# SOS.net
KiCad netlist of a schematic drawn in EAGLE
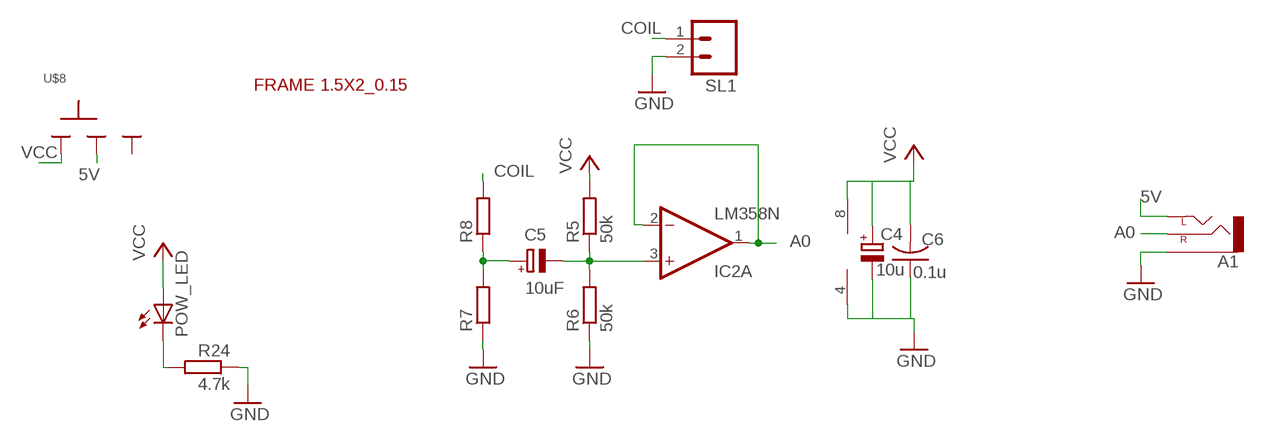
[diagram p0: schematic, sheet 1]

(export (version "E")
  (design (tool "Eeschema 10.0.6"))
  (components
    (comp (ref "A1")
      (value "AUDIO-JACKPTH")
      (footprint "eagle-import:AUDIO-JACK")
      (libsource (lib "eagle-import") (part "AUDIO-JACKPTH"))
    )
    (comp (ref "C4")
      (value "10u")
      (footprint "eagle-import:E2,5-5")
      (libsource (lib "eagle-import") (part "CPOL-EUE2.5-5"))
    )
    (comp (ref "C5")
      (value "10uF")
      (footprint "eagle-import:E2,5-6")
      (libsource (lib "eagle-import") (part "CPOL-EUE2.5-6"))
    )
    (comp (ref "C6")
      (value "0.1u")
      (footprint "eagle-import:C025-024X044")
      (libsource (lib "eagle-import") (part "C-US025-024X044"))
    )
    (comp (ref "IC2")
      (value "LM358N")
      (footprint "eagle-import:DIL08")
      (libsource (lib "eagle-import") (part "LM358N"))
    )
    (comp (ref "POW_LED")
      (value "LED3MM")
      (footprint "eagle-import:LED3MM")
      (libsource (lib "eagle-import") (part "LED3MM"))
    )
    (comp (ref "R5")
      (value "50k")
      (footprint "eagle-import:0204_7")
      (libsource (lib "eagle-import") (part "R-EU_0204/7"))
    )
    (comp (ref "R6")
      (value "50k")
      (footprint "eagle-import:0204_7")
      (libsource (lib "eagle-import") (part "R-EU_0204/7"))
    )
    (comp (ref "R7")
      (value "R-EU_0204/7")
      (footprint "eagle-import:0204_7")
      (libsource (lib "eagle-import") (part "R-EU_0204/7"))
    )
    (comp (ref "R8")
      (value "R-EU_0204/7")
      (footprint "eagle-import:0204_7")
      (libsource (lib "eagle-import") (part "R-EU_0204/7"))
    )
    (comp (ref "R24")
      (value "4.7k")
      (footprint "eagle-import:0204_7")
      (libsource (lib "eagle-import") (part "R-EU_0204/7"))
    )
    (comp (ref "SL1")
      (value "M02")
      (footprint "eagle-import:02P")
      (libsource (lib "eagle-import") (part "M02"))
    )
    (comp (ref "U$1")
      (value "FRAME_1.5X2_RAD_0.15")
      (footprint "eagle-import:FRAME_1.5X2_RAD_0.15")
      (libsource (lib "eagle-import") (part "FRAME_1.5X2_RAD_0.15"))
    )
    (comp (ref "U$8")
      (value "SLIDESWITCH-BIG")
      (footprint "eagle-import:BIGSWITCH")
      (libsource (lib "eagle-import") (part "SLIDESWITCH-BIG"))
    )
  )
  (nets
    (net (code "1") (name "/5V") (class "Default")
      (node (ref "A1") (pin "TIP") (pinfunction "LEFT_TIP") (pintype "bidirectional"))
      (node (ref "U$8") (pin "2") (pinfunction "2_2") (pintype "bidirectional"))
    )
    (net (code "2") (name "/A0") (class "Default")
      (node (ref "A1") (pin "RING") (pinfunction "RIGHT_RING") (pintype "bidirectional"))
      (node (ref "IC2") (pin "1") (pinfunction "OUT_1") (pintype "output"))
      (node (ref "IC2") (pin "2") (pinfunction "-IN_2") (pintype "input"))
    )
    (net (code "3") (name "/COIL") (class "Default")
      (node (ref "R8") (pin "2") (pinfunction "2_2") (pintype "passive"))
      (node (ref "SL1") (pin "1") (pinfunction "1_1") (pintype "passive"))
    )
    (net (code "4") (name "GND") (class "Default")
      (node (ref "A1") (pin "SLEEVE") (pinfunction "SLEEVE_SLEEVE") (pintype "bidirectional"))
      (node (ref "C4") (pin "-") (pinfunction "-_-") (pintype "passive"))
      (node (ref "C6") (pin "1") (pinfunction "1_1") (pintype "passive"))
      (node (ref "IC2") (pin "4") (pinfunction "V-_4") (pintype "power_in"))
      (node (ref "R24") (pin "1") (pinfunction "1_1") (pintype "passive"))
      (node (ref "R6") (pin "1") (pinfunction "1_1") (pintype "passive"))
      (node (ref "R7") (pin "1") (pinfunction "1_1") (pintype "passive"))
      (node (ref "SL1") (pin "2") (pinfunction "2_2") (pintype "passive"))
    )
    (net (code "5") (name "Net-(C5-Pad+)") (class "Default")
      (node (ref "C5") (pin "+") (pinfunction "+_+") (pintype "passive"))
      (node (ref "R7") (pin "2") (pinfunction "2_2") (pintype "passive"))
      (node (ref "R8") (pin "1") (pinfunction "1_1") (pintype "passive"))
    )
    (net (code "6") (name "Net-(IC2A-+IN)") (class "Default")
      (node (ref "C5") (pin "-") (pinfunction "-_-") (pintype "passive"))
      (node (ref "IC2") (pin "3") (pinfunction "+IN_3") (pintype "input"))
      (node (ref "R5") (pin "1") (pinfunction "1_1") (pintype "passive"))
      (node (ref "R6") (pin "2") (pinfunction "2_2") (pintype "passive"))
    )
    (net (code "7") (name "Net-(POW_LED-C)") (class "Default")
      (node (ref "POW_LED") (pin "K") (pinfunction "C_K") (pintype "passive"))
      (node (ref "R24") (pin "2") (pinfunction "2_2") (pintype "passive"))
    )
    (net (code "8") (name "VCC") (class "Default")
      (node (ref "C4") (pin "+") (pinfunction "+_+") (pintype "passive"))
      (node (ref "C6") (pin "2") (pinfunction "2_2") (pintype "passive"))
      (node (ref "IC2") (pin "8") (pinfunction "V+_8") (pintype "power_in"))
      (node (ref "POW_LED") (pin "A") (pinfunction "A_A") (pintype "passive"))
      (node (ref "R5") (pin "2") (pinfunction "2_2") (pintype "passive"))
      (node (ref "U$8") (pin "1") (pinfunction "1_1") (pintype "bidirectional"))
    )
    (net (code "9") (name "unconnected-(U$8-Pad3)") (class "Default")
      (node (ref "U$8") (pin "3") (pinfunction "3_3") (pintype "bidirectional"))
    )
  )
)
